# Pg02__AM335X_Section_1.net
KiCad netlist of a schematic drawn in Altium Designer
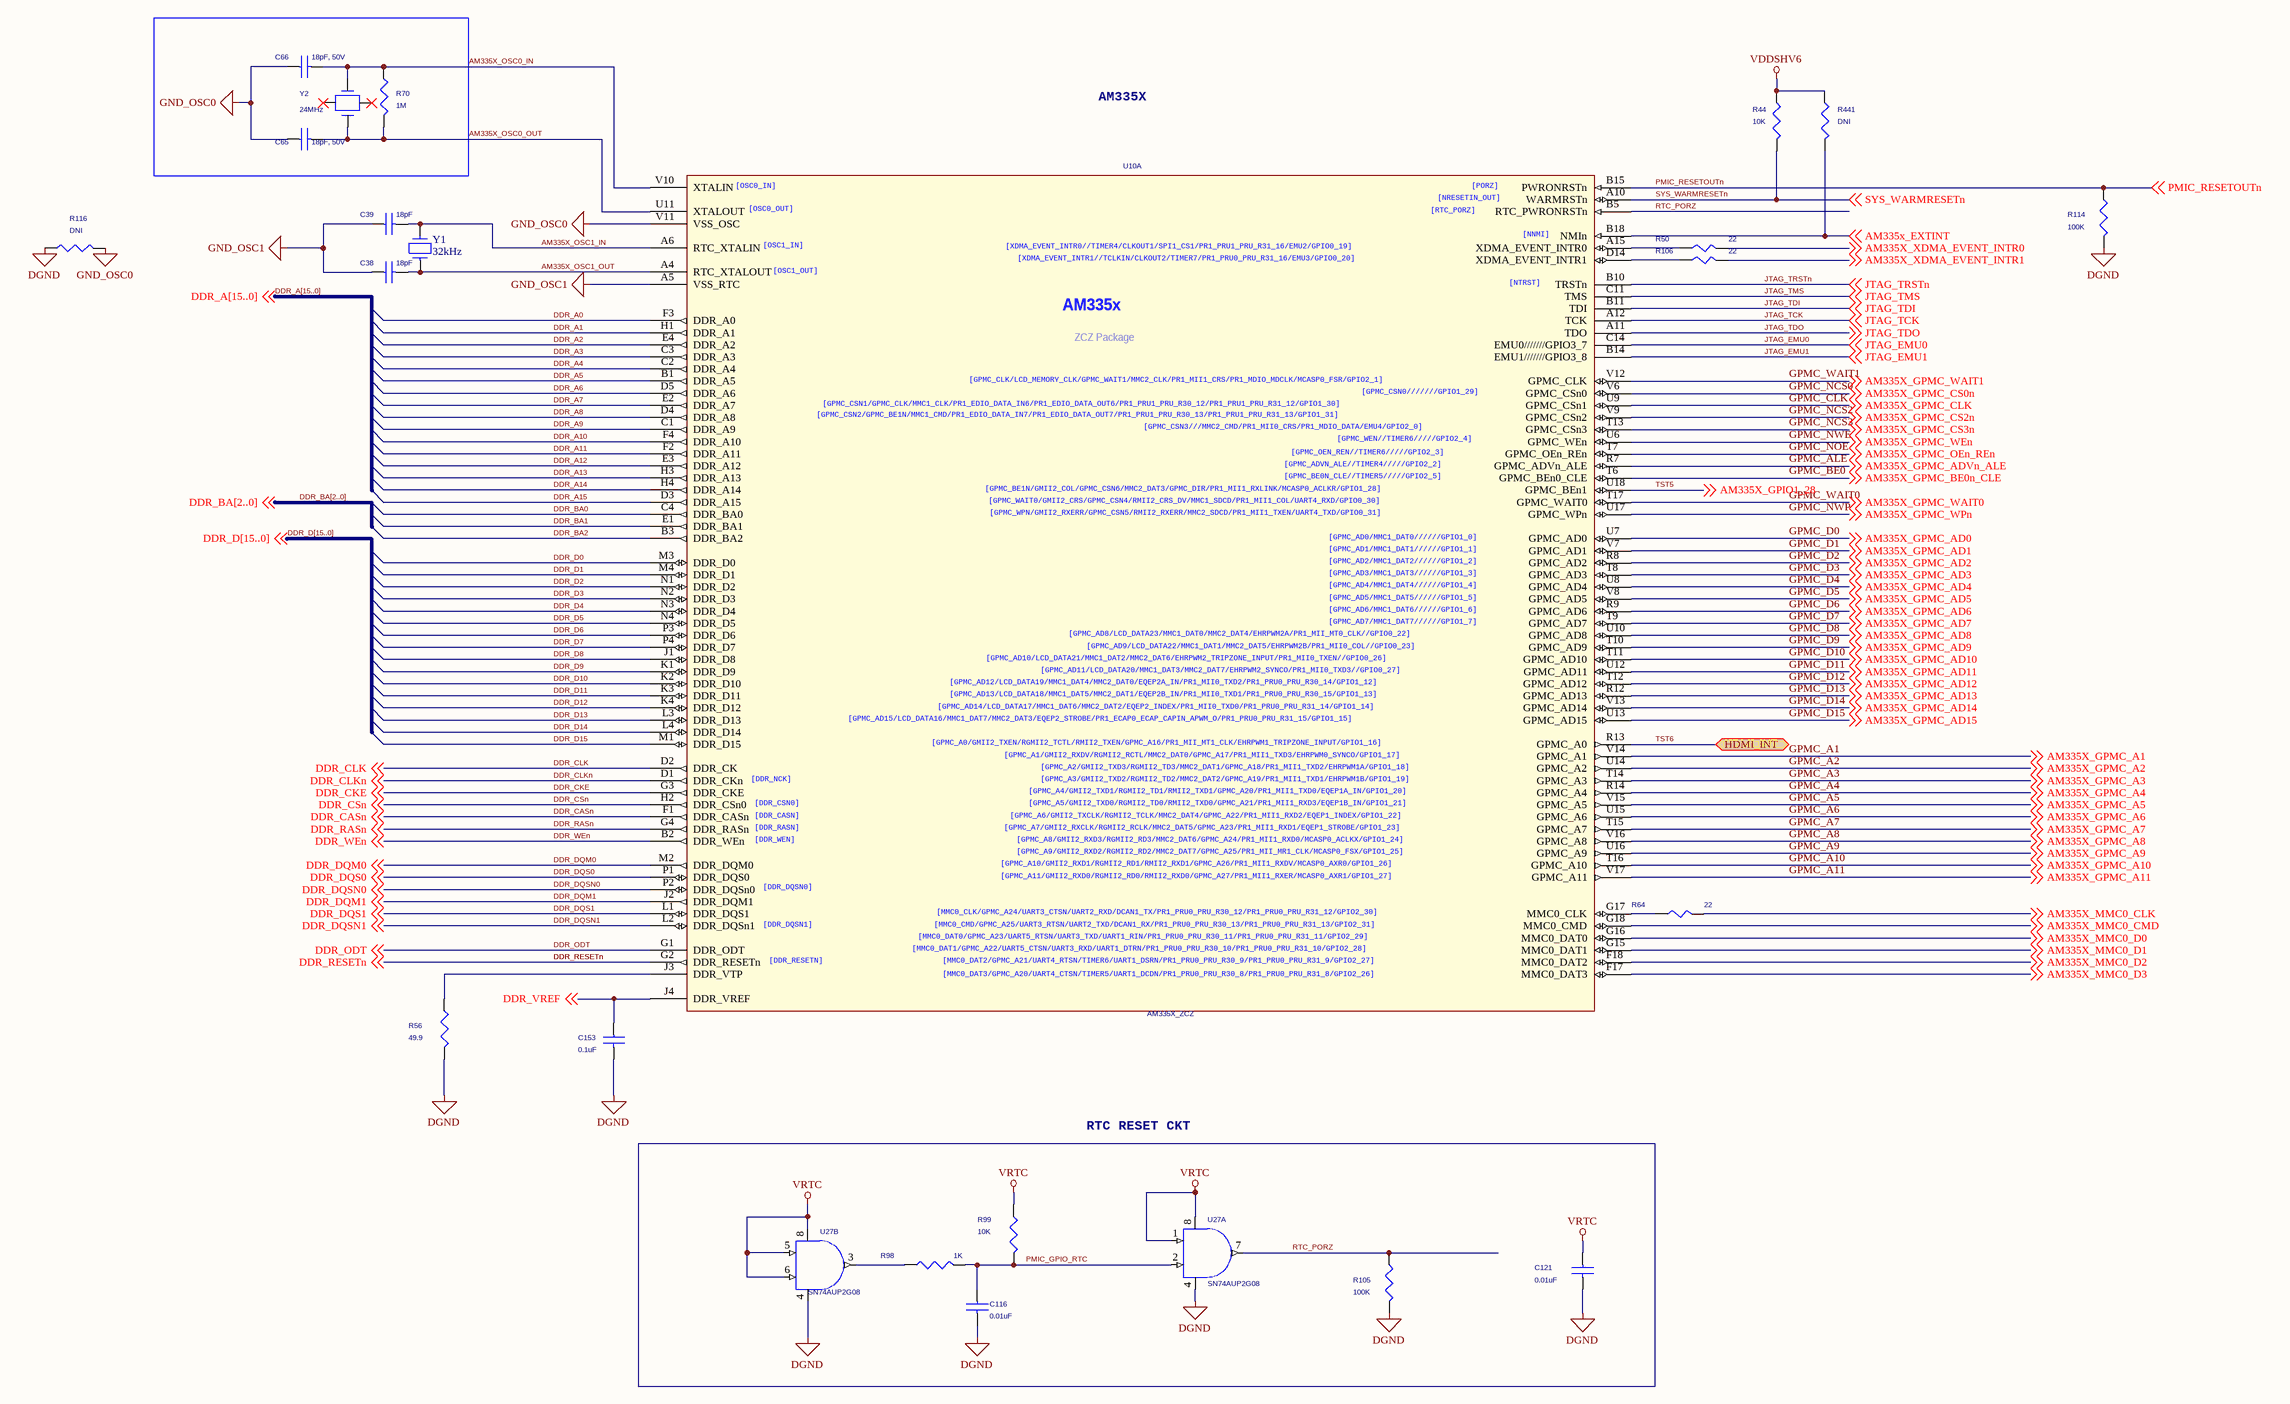
[diagram p0: Pg02_ AM335X Section 1 .SchDoc]

(export (version "E")
  (design (tool "Eeschema 10.0.6"))
  (components
    (comp (ref "C38")
      (value "18pF")
      (footprint "SM-7351-CAP-0402")
      (description "Capacitor 22pF 50V 10% 0402")
      (fields (field (name "MFR") "Panasonic") (field (name "TIINTPARTNUMBER") "1C0020"))
      (libsource (lib "*") (part "22pFCapacitor50V10%SMD0402"))
    )
    (comp (ref "C39")
      (value "18pF")
      (footprint "SM-7351-CAP-0402")
      (description "Capacitor 22pF 50V 10% 0402")
      (fields (field (name "MFR") "Panasonic") (field (name "TIINTPARTNUMBER") "1C0020"))
      (libsource (lib "*") (part "22pFCapacitor50V10%SMD0402"))
    )
    (comp (ref "C65")
      (value "18pF, 50V")
      (footprint "SM-7351-CAP-0402")
      (fields (field (name "MFR") "TDK") (field (name "TIINTPARTNUMBER") "1C0119"))
      (libsource (lib "*") (part "18pFCapacitor50V5%0402"))
    )
    (comp (ref "C66")
      (value "18pF, 50V")
      (footprint "SM-7351-CAP-0402")
      (fields (field (name "MFR") "TDK") (field (name "TIINTPARTNUMBER") "1C0119"))
      (libsource (lib "*") (part "18pFCapacitor50V5%0402"))
    )
    (comp (ref "C116")
      (value "0.01uF")
      (footprint "SM-7351-CAP-0402")
      (fields (field (name "MFR") "Panasonic") (field (name "TIINTPARTNUMBER") "1C0012"))
      (libsource (lib "*") (part "0.01uFCapacitor16V10%0402"))
    )
    (comp (ref "C121")
      (value "0.01uF")
      (footprint "SM-7351-CAP-0402")
      (fields (field (name "MFR") "Panasonic") (field (name "TIINTPARTNUMBER") "1C0012"))
      (libsource (lib "*") (part "0.01uFCapacitor16V10%0402"))
    )
    (comp (ref "C153")
      (value "0.1uF")
      (footprint "SM-7351-CAP-0402")
      (fields (field (name "TIINTPARTNUMBER") "1C0089") (field (name "MFR") "Kemet"))
      (libsource (lib "*") (part "0.1uFCapacitor16V10%0402_Dup1"))
    )
    (comp (ref "R44")
      (value "10K")
      (footprint "SM-7351-RES-0402")
      (description "Resistor 10Kohm 1/16W 5% 0402")
      (fields (field (name "TIINTPARTNUMBER") "1R0168") (field (name "MFR") "Rohm"))
      (libsource (lib "*") (part "10KOhmResistor1/16W0402_Dup1"))
    )
    (comp (ref "R50")
      (value "22")
      (footprint "SM-7351-RES-0402")
      (description "Resistor 22 ohm 1/16W 1% 0402")
      (fields (field (name "MFR") "ROHM") (field (name "TIINTPARTNUMBER") "1R0175"))
      (libsource (lib "*") (part "22OhmResistor1/16W1%0402"))
    )
    (comp (ref "R56")
      (value "49.9")
      (footprint "smd_melf0102")
      (fields (field (name "MFR") "Vishay") (field (name "TIINTPARTNUMBER") "1R0243"))
      (libsource (lib "*") (part "49.9ohm1/3W1%SMDMELF0102"))
    )
    (comp (ref "R64")
      (value "22")
      (footprint "SM-7351-RES-0402")
      (description "Resistor 22 ohm 1/16W 1% 0402")
      (fields (field (name "MFR") "ROHM") (field (name "TIINTPARTNUMBER") "1R0175"))
      (libsource (lib "*") (part "22OhmResistor1/16W1%0402"))
    )
    (comp (ref "R70")
      (value "1M")
      (footprint "SM-7351-RES-0402")
      (fields (field (name "MFR") "Stackpole Electronics") (field (name "TIINTPARTNUMBER") "1R0182"))
      (libsource (lib "*") (part "1MOhmResistor1/16W0402"))
    )
    (comp (ref "R98")
      (value "1K")
      (footprint "SM-7351-RES-0402")
      (description "Resistor 1Kohm 1/16W 5% 0402")
      (fields (field (name "MFR") "Panasonic") (field (name "TIINTPARTNUMBER") "1R0027"))
      (libsource (lib "*") (part "1KOhmResistor1/16W0402"))
    )
    (comp (ref "R99")
      (value "10K")
      (footprint "SM-7351-RES-0402")
      (description "Resistor 10Kohm 1/16W 5% 0402")
      (fields (field (name "MFR") "Rohm") (field (name "TIINTPARTNUMBER") "1R0168"))
      (libsource (lib "*") (part "10KOhmResistor1/16W0402"))
    )
    (comp (ref "R105")
      (value "100K")
      (footprint "SM-7351-RES-0402")
      (fields (field (name "TIINTPARTNUMBER") "1R0181") (field (name "MFR") "Stackpole Electronics"))
      (libsource (lib "*") (part "100KOhmResistor1/16W0402"))
    )
    (comp (ref "R106")
      (value "22")
      (footprint "SM-7351-RES-0402")
      (description "Resistor 22 ohm 1/16W 1% 0402")
      (fields (field (name "MFR") "ROHM") (field (name "TIINTPARTNUMBER") "1R0175"))
      (libsource (lib "*") (part "22OhmResistor1/16W1%0402"))
    )
    (comp (ref "R114")
      (value "100K")
      (footprint "SM-7351-RES-0402")
      (fields (field (name "TIINTPARTNUMBER") "1R0181") (field (name "MFR") "Stackpole Electronics"))
      (libsource (lib "*") (part "100KOhmResistor1/16W0402"))
    )
    (comp (ref "R116")
      (value "DNI")
      (footprint "SM-7351-RES-0402")
      (fields (field (name "MFR") "Stackpole Electronics") (field (name "TIINTPARTNUMBER") "1R0182"))
      (libsource (lib "*") (part "1MOhmResistor1/16W0402"))
    )
    (comp (ref "R441")
      (value "DNI")
      (footprint "SM-7351-RES-0402")
      (description "Resistor 10Kohm 1/16W 5% 0402")
      (fields (field (name "TIINTPARTNUMBER") "1R0168") (field (name "MFR") "Rohm"))
      (libsource (lib "*") (part "10KOhmResistor1/16W0402_Dup1"))
    )
    (comp (ref "U10")
      (value "AM335X_ZCZ")
      (footprint "BGA15X15-324-55M")
      (fields (field (name "TIINTPARTNUMBER") "1A0242") (field (name "MFR") "TI"))
      (libsource (lib "*") (part "AM335X_15mmx15mm"))
    )
    (comp (ref "U27")
      (value "SN74AUP2G08")
      (footprint "U_8_DCU")
      (description "Low Power Dual AND Gate")
      (fields (field (name "TIINTPARTNUMBER") "1A0249") (field (name "MFR") "TI"))
      (libsource (lib "*") (part "SN74AUP2G08"))
    )
    (comp (ref "Y1")
      (value "32kHz")
      (footprint "Xtal 3215")
      (description "CRYSTAL")
      (libsource (lib "Fireflash_B") (part "CRYSTAL"))
    )
    (comp (ref "Y2")
      (value "24MHz")
      (footprint "XTAL4_3P2X2P5_SMD")
      (fields (field (name "MFR") "Citizen") (field (name "TIINTPARTNUMBER") "1Y0039"))
      (libsource (lib "*") (part "Crystal24MHz18PFsmd_0"))
    )
  )
  (nets
    (net (code "1") (name "/AM335X_OSC0_IN") (class "Default")
      (node (ref "C66") (pin "2") (pinfunction "2_2") (pintype "passive"))
      (node (ref "R70") (pin "2") (pinfunction "P2_2") (pintype "passive"))
      (node (ref "U10") (pin "V10") (pinfunction "XTALIN_V10") (pintype "passive"))
      (node (ref "Y2") (pin "3") (pinfunction "3_3") (pintype "passive"))
    )
    (net (code "2") (name "/AM335X_OSC0_OUT") (class "Default")
      (node (ref "C65") (pin "2") (pinfunction "2_2") (pintype "passive"))
      (node (ref "R70") (pin "1") (pinfunction "P1_1") (pintype "passive"))
      (node (ref "U10") (pin "U11") (pinfunction "XTALOUT_U11") (pintype "passive"))
      (node (ref "Y2") (pin "1") (pinfunction "1_1") (pintype "passive"))
    )
    (net (code "3") (name "/AM335X_OSC1_IN") (class "Default")
      (node (ref "C39") (pin "2") (pinfunction "2_2") (pintype "passive"))
      (node (ref "U10") (pin "A6") (pinfunction "RTC_XTALIN_A6") (pintype "passive"))
      (node (ref "Y1") (pin "2") (pintype "passive"))
    )
    (net (code "4") (name "/AM335X_OSC1_OUT") (class "Default")
      (node (ref "C38") (pin "2") (pinfunction "2_2") (pintype "passive"))
      (node (ref "U10") (pin "A4") (pinfunction "RTC_XTALOUT_A4") (pintype "passive"))
      (node (ref "Y1") (pin "1") (pintype "passive"))
    )
    (net (code "5") (name "/PMIC_GPIO_RTC") (class "Default")
      (node (ref "C116") (pin "1") (pinfunction "1_1") (pintype "passive"))
      (node (ref "R98") (pin "1") (pinfunction "P1_1") (pintype "passive"))
      (node (ref "R99") (pin "1") (pinfunction "P1_1") (pintype "passive"))
      (node (ref "U27") (pin "2") (pinfunction "2B_2") (pintype "input"))
    )
    (net (code "6") (name "/RTC_PORZ") (class "Default")
      (node (ref "R105") (pin "2") (pinfunction "P2_2") (pintype "passive"))
      (node (ref "U10") (pin "B5") (pinfunction "RTC_PWRONRSTn_B5") (pintype "input"))
      (node (ref "U27") (pin "7") (pinfunction "2Y_7") (pintype "output"))
    )
    (net (code "7") (name "/TST6") (class "Default")
      (node (ref "U10") (pin "R13") (pinfunction "GPMC_A0_R13") (pintype "output"))
    )
    (net (code "8") (name "AM335X_GPIO1_28") (class "Default")
      (node (ref "U10") (pin "U18") (pinfunction "GPMC_BEn1_U18") (pintype "bidirectional"))
    )
    (net (code "9") (name "AM335X_GPMC_A1") (class "Default")
      (node (ref "U10") (pin "V14") (pinfunction "GPMC_A1_V14") (pintype "output"))
    )
    (net (code "10") (name "AM335X_GPMC_A2") (class "Default")
      (node (ref "U10") (pin "U14") (pinfunction "GPMC_A2_U14") (pintype "output"))
    )
    (net (code "11") (name "AM335X_GPMC_A3") (class "Default")
      (node (ref "U10") (pin "T14") (pinfunction "GPMC_A3_T14") (pintype "output"))
    )
    (net (code "12") (name "AM335X_GPMC_A4") (class "Default")
      (node (ref "U10") (pin "R14") (pinfunction "GPMC_A4_R14") (pintype "output"))
    )
    (net (code "13") (name "AM335X_GPMC_A5") (class "Default")
      (node (ref "U10") (pin "V15") (pinfunction "GPMC_A5_V15") (pintype "output"))
    )
    (net (code "14") (name "AM335X_GPMC_A6") (class "Default")
      (node (ref "U10") (pin "U15") (pinfunction "GPMC_A6_U15") (pintype "output"))
    )
    (net (code "15") (name "AM335X_GPMC_A7") (class "Default")
      (node (ref "U10") (pin "T15") (pinfunction "GPMC_A7_T15") (pintype "output"))
    )
    (net (code "16") (name "AM335X_GPMC_A8") (class "Default")
      (node (ref "U10") (pin "V16") (pinfunction "GPMC_A8_V16") (pintype "output"))
    )
    (net (code "17") (name "AM335X_GPMC_A9") (class "Default")
      (node (ref "U10") (pin "U16") (pinfunction "GPMC_A9_U16") (pintype "output"))
    )
    (net (code "18") (name "AM335X_GPMC_A10") (class "Default")
      (node (ref "U10") (pin "T16") (pinfunction "GPMC_A10_T16") (pintype "output"))
    )
    (net (code "19") (name "AM335X_GPMC_A11") (class "Default")
      (node (ref "U10") (pin "V17") (pinfunction "GPMC_A11_V17") (pintype "output"))
    )
    (net (code "20") (name "AM335X_GPMC_AD0") (class "Default")
      (node (ref "U10") (pin "U7") (pinfunction "GPMC_AD0_U7") (pintype "bidirectional"))
    )
    (net (code "21") (name "AM335X_GPMC_AD1") (class "Default")
      (node (ref "U10") (pin "V7") (pinfunction "GPMC_AD1_V7") (pintype "bidirectional"))
    )
    (net (code "22") (name "AM335X_GPMC_AD2") (class "Default")
      (node (ref "U10") (pin "R8") (pinfunction "GPMC_AD2_R8") (pintype "bidirectional"))
    )
    (net (code "23") (name "AM335X_GPMC_AD3") (class "Default")
      (node (ref "U10") (pin "T8") (pinfunction "GPMC_AD3_T8") (pintype "bidirectional"))
    )
    (net (code "24") (name "AM335X_GPMC_AD4") (class "Default")
      (node (ref "U10") (pin "U8") (pinfunction "GPMC_AD4_U8") (pintype "bidirectional"))
    )
    (net (code "25") (name "AM335X_GPMC_AD5") (class "Default")
      (node (ref "U10") (pin "V8") (pinfunction "GPMC_AD5_V8") (pintype "bidirectional"))
    )
    (net (code "26") (name "AM335X_GPMC_AD6") (class "Default")
      (node (ref "U10") (pin "R9") (pinfunction "GPMC_AD6_R9") (pintype "bidirectional"))
    )
    (net (code "27") (name "AM335X_GPMC_AD7") (class "Default")
      (node (ref "U10") (pin "T9") (pinfunction "GPMC_AD7_T9") (pintype "bidirectional"))
    )
    (net (code "28") (name "AM335X_GPMC_AD8") (class "Default")
      (node (ref "U10") (pin "U10") (pinfunction "GPMC_AD8_U10") (pintype "bidirectional"))
    )
    (net (code "29") (name "AM335X_GPMC_AD9") (class "Default")
      (node (ref "U10") (pin "T10") (pinfunction "GPMC_AD9_T10") (pintype "bidirectional"))
    )
    (net (code "30") (name "AM335X_GPMC_AD10") (class "Default")
      (node (ref "U10") (pin "T11") (pinfunction "GPMC_AD10_T11") (pintype "bidirectional"))
    )
    (net (code "31") (name "AM335X_GPMC_AD11") (class "Default")
      (node (ref "U10") (pin "U12") (pinfunction "GPMC_AD11_U12") (pintype "bidirectional"))
    )
    (net (code "32") (name "AM335X_GPMC_AD12") (class "Default")
      (node (ref "U10") (pin "T12") (pinfunction "GPMC_AD12_T12") (pintype "bidirectional"))
    )
    (net (code "33") (name "AM335X_GPMC_AD13") (class "Default")
      (node (ref "U10") (pin "R12") (pinfunction "GPMC_AD13_R12") (pintype "bidirectional"))
    )
    (net (code "34") (name "AM335X_GPMC_AD14") (class "Default")
      (node (ref "U10") (pin "V13") (pinfunction "GPMC_AD14_V13") (pintype "bidirectional"))
    )
    (net (code "35") (name "AM335X_GPMC_AD15") (class "Default")
      (node (ref "U10") (pin "U13") (pinfunction "GPMC_AD15_U13") (pintype "bidirectional"))
    )
    (net (code "36") (name "AM335X_GPMC_ADVn_ALE") (class "Default")
      (node (ref "U10") (pin "R7") (pinfunction "GPMC_ADVn_ALE_R7") (pintype "bidirectional"))
    )
    (net (code "37") (name "AM335X_GPMC_BE0n_CLE") (class "Default")
      (node (ref "U10") (pin "T6") (pinfunction "GPMC_BEn0_CLE_T6") (pintype "bidirectional"))
    )
    (net (code "38") (name "AM335X_GPMC_CLK") (class "Default")
      (node (ref "U10") (pin "U9") (pinfunction "GPMC_CSn1_U9") (pintype "bidirectional"))
    )
    (net (code "39") (name "AM335X_GPMC_CS0n") (class "Default")
      (node (ref "U10") (pin "V6") (pinfunction "GPMC_CSn0_V6") (pintype "bidirectional"))
    )
    (net (code "40") (name "AM335X_GPMC_CS2n") (class "Default")
      (node (ref "U10") (pin "V9") (pinfunction "GPMC_CSn2_V9") (pintype "bidirectional"))
    )
    (net (code "41") (name "AM335X_GPMC_CS3n") (class "Default")
      (node (ref "U10") (pin "T13") (pinfunction "GPMC_CSn3_T13") (pintype "bidirectional"))
    )
    (net (code "42") (name "AM335X_GPMC_OEn_REn") (class "Default")
      (node (ref "U10") (pin "T7") (pinfunction "GPMC_OEn_REn_T7") (pintype "bidirectional"))
    )
    (net (code "43") (name "AM335X_GPMC_WAIT0") (class "Default")
      (node (ref "U10") (pin "T17") (pinfunction "GPMC_WAIT0_T17") (pintype "bidirectional"))
    )
    (net (code "44") (name "AM335X_GPMC_WAIT1") (class "Default")
      (node (ref "U10") (pin "V12") (pinfunction "GPMC_CLK_V12") (pintype "bidirectional"))
    )
    (net (code "45") (name "AM335X_GPMC_WEn") (class "Default")
      (node (ref "U10") (pin "U6") (pinfunction "GPMC_WEn_U6") (pintype "bidirectional"))
    )
    (net (code "46") (name "AM335X_GPMC_WPn") (class "Default")
      (node (ref "U10") (pin "U17") (pinfunction "GPMC_WPn_U17") (pintype "bidirectional"))
    )
    (net (code "47") (name "AM335X_MMC0_CLK") (class "Default")
      (node (ref "R64") (pin "1") (pinfunction "P1_1") (pintype "passive"))
    )
    (net (code "48") (name "AM335X_MMC0_CMD") (class "Default")
      (node (ref "U10") (pin "G18") (pinfunction "MMC0_CMD_G18") (pintype "bidirectional"))
    )
    (net (code "49") (name "AM335X_MMC0_D0") (class "Default")
      (node (ref "U10") (pin "G16") (pinfunction "MMC0_DAT0_G16") (pintype "bidirectional"))
    )
    (net (code "50") (name "AM335X_MMC0_D1") (class "Default")
      (node (ref "U10") (pin "G15") (pinfunction "MMC0_DAT1_G15") (pintype "bidirectional"))
    )
    (net (code "51") (name "AM335X_MMC0_D2") (class "Default")
      (node (ref "U10") (pin "F18") (pinfunction "MMC0_DAT2_F18") (pintype "bidirectional"))
    )
    (net (code "52") (name "AM335X_MMC0_D3") (class "Default")
      (node (ref "U10") (pin "F17") (pinfunction "MMC0_DAT3_F17") (pintype "bidirectional"))
    )
    (net (code "53") (name "AM335X_XDMA_EVENT_INTR0") (class "Default")
      (node (ref "R50") (pin "1") (pinfunction "P1_1") (pintype "passive"))
    )
    (net (code "54") (name "AM335X_XDMA_EVENT_INTR1") (class "Default")
      (node (ref "R106") (pin "1") (pinfunction "P1_1") (pintype "passive"))
    )
    (net (code "55") (name "AM335x_EXTINT") (class "Default")
      (node (ref "R441") (pin "1") (pinfunction "P1_1") (pintype "passive"))
      (node (ref "U10") (pin "B18") (pinfunction "NMIn_B18") (pintype "input"))
    )
    (net (code "56") (name "DDR_A0") (class "Default")
      (node (ref "U10") (pin "F3") (pinfunction "DDR_A0_F3") (pintype "output"))
    )
    (net (code "57") (name "DDR_A1") (class "Default")
      (node (ref "U10") (pin "H1") (pinfunction "DDR_A1_H1") (pintype "output"))
    )
    (net (code "58") (name "DDR_A2") (class "Default")
      (node (ref "U10") (pin "E4") (pinfunction "DDR_A2_E4") (pintype "output"))
    )
    (net (code "59") (name "DDR_A3") (class "Default")
      (node (ref "U10") (pin "C3") (pinfunction "DDR_A3_C3") (pintype "output"))
    )
    (net (code "60") (name "DDR_A4") (class "Default")
      (node (ref "U10") (pin "C2") (pinfunction "DDR_A4_C2") (pintype "output"))
    )
    (net (code "61") (name "DDR_A5") (class "Default")
      (node (ref "U10") (pin "B1") (pinfunction "DDR_A5_B1") (pintype "output"))
    )
    (net (code "62") (name "DDR_A6") (class "Default")
      (node (ref "U10") (pin "D5") (pinfunction "DDR_A6_D5") (pintype "output"))
    )
    (net (code "63") (name "DDR_A7") (class "Default")
      (node (ref "U10") (pin "E2") (pinfunction "DDR_A7_E2") (pintype "output"))
    )
    (net (code "64") (name "DDR_A8") (class "Default")
      (node (ref "U10") (pin "D4") (pinfunction "DDR_A8_D4") (pintype "output"))
    )
    (net (code "65") (name "DDR_A9") (class "Default")
      (node (ref "U10") (pin "C1") (pinfunction "DDR_A9_C1") (pintype "output"))
    )
    (net (code "66") (name "DDR_A10") (class "Default")
      (node (ref "U10") (pin "F4") (pinfunction "DDR_A10_F4") (pintype "output"))
    )
    (net (code "67") (name "DDR_A11") (class "Default")
      (node (ref "U10") (pin "F2") (pinfunction "DDR_A11_F2") (pintype "output"))
    )
    (net (code "68") (name "DDR_A12") (class "Default")
      (node (ref "U10") (pin "E3") (pinfunction "DDR_A12_E3") (pintype "output"))
    )
    (net (code "69") (name "DDR_A13") (class "Default")
      (node (ref "U10") (pin "H3") (pinfunction "DDR_A13_H3") (pintype "output"))
    )
    (net (code "70") (name "DDR_A14") (class "Default")
      (node (ref "U10") (pin "H4") (pinfunction "DDR_A14_H4") (pintype "output"))
    )
    (net (code "71") (name "DDR_A15") (class "Default")
      (node (ref "U10") (pin "D3") (pinfunction "DDR_A15_D3") (pintype "output"))
    )
    (net (code "73") (name "DDR_BA0") (class "Default")
      (node (ref "U10") (pin "C4") (pinfunction "DDR_BA0_C4") (pintype "output"))
    )
    (net (code "74") (name "DDR_BA1") (class "Default")
      (node (ref "U10") (pin "E1") (pinfunction "DDR_BA1_E1") (pintype "output"))
    )
    (net (code "75") (name "DDR_BA2") (class "Default")
      (node (ref "U10") (pin "B3") (pinfunction "DDR_BA2_B3") (pintype "output"))
    )
    (net (code "77") (name "DDR_CASn") (class "Default")
      (node (ref "U10") (pin "F1") (pinfunction "DDR_CASn_F1") (pintype "output"))
    )
    (net (code "78") (name "DDR_CKE") (class "Default")
      (node (ref "U10") (pin "G3") (pinfunction "DDR_CKE_G3") (pintype "output"))
    )
    (net (code "79") (name "DDR_CLK") (class "Default")
      (node (ref "U10") (pin "D2") (pinfunction "DDR_CK_D2") (pintype "output"))
    )
    (net (code "80") (name "DDR_CLKn") (class "Default")
      (node (ref "U10") (pin "D1") (pinfunction "DDR_CKn_D1") (pintype "output"))
    )
    (net (code "81") (name "DDR_CSn") (class "Default")
      (node (ref "U10") (pin "H2") (pinfunction "DDR_CSn0_H2") (pintype "output"))
    )
    (net (code "82") (name "DDR_D0") (class "Default")
      (node (ref "U10") (pin "M3") (pinfunction "DDR_D0_M3") (pintype "bidirectional"))
    )
    (net (code "83") (name "DDR_D1") (class "Default")
      (node (ref "U10") (pin "M4") (pinfunction "DDR_D1_M4") (pintype "bidirectional"))
    )
    (net (code "84") (name "DDR_D2") (class "Default")
      (node (ref "U10") (pin "N1") (pinfunction "DDR_D2_N1") (pintype "bidirectional"))
    )
    (net (code "85") (name "DDR_D3") (class "Default")
      (node (ref "U10") (pin "N2") (pinfunction "DDR_D3_N2") (pintype "bidirectional"))
    )
    (net (code "86") (name "DDR_D4") (class "Default")
      (node (ref "U10") (pin "N3") (pinfunction "DDR_D4_N3") (pintype "bidirectional"))
    )
    (net (code "87") (name "DDR_D5") (class "Default")
      (node (ref "U10") (pin "N4") (pinfunction "DDR_D5_N4") (pintype "bidirectional"))
    )
    (net (code "88") (name "DDR_D6") (class "Default")
      (node (ref "U10") (pin "P3") (pinfunction "DDR_D6_P3") (pintype "bidirectional"))
    )
    (net (code "89") (name "DDR_D7") (class "Default")
      (node (ref "U10") (pin "P4") (pinfunction "DDR_D7_P4") (pintype "bidirectional"))
    )
    (net (code "90") (name "DDR_D8") (class "Default")
      (node (ref "U10") (pin "J1") (pinfunction "DDR_D8_J1") (pintype "bidirectional"))
    )
    (net (code "91") (name "DDR_D9") (class "Default")
      (node (ref "U10") (pin "K1") (pinfunction "DDR_D9_K1") (pintype "bidirectional"))
    )
    (net (code "92") (name "DDR_D10") (class "Default")
      (node (ref "U10") (pin "K2") (pinfunction "DDR_D10_K2") (pintype "bidirectional"))
    )
    (net (code "93") (name "DDR_D11") (class "Default")
      (node (ref "U10") (pin "K3") (pinfunction "DDR_D11_K3") (pintype "bidirectional"))
    )
    (net (code "94") (name "DDR_D12") (class "Default")
      (node (ref "U10") (pin "K4") (pinfunction "DDR_D12_K4") (pintype "bidirectional"))
    )
    (net (code "95") (name "DDR_D13") (class "Default")
      (node (ref "U10") (pin "L3") (pinfunction "DDR_D13_L3") (pintype "bidirectional"))
    )
    (net (code "96") (name "DDR_D14") (class "Default")
      (node (ref "U10") (pin "L4") (pinfunction "DDR_D14_L4") (pintype "bidirectional"))
    )
    (net (code "97") (name "DDR_D15") (class "Default")
      (node (ref "U10") (pin "M1") (pinfunction "DDR_D15_M1") (pintype "bidirectional"))
    )
    (net (code "98") (name "DDR_DQM0") (class "Default")
      (node (ref "U10") (pin "M2") (pinfunction "DDR_DQM0_M2") (pintype "output"))
    )
    (net (code "99") (name "DDR_DQM1") (class "Default")
      (node (ref "U10") (pin "J2") (pinfunction "DDR_DQM1_J2") (pintype "output"))
    )
    (net (code "100") (name "DDR_DQS0") (class "Default")
      (node (ref "U10") (pin "P1") (pinfunction "DDR_DQS0_P1") (pintype "bidirectional"))
    )
    (net (code "101") (name "DDR_DQS1") (class "Default")
      (node (ref "U10") (pin "L1") (pinfunction "DDR_DQS1_L1") (pintype "bidirectional"))
    )
    (net (code "102") (name "DDR_DQSN0") (class "Default")
      (node (ref "U10") (pin "P2") (pinfunction "DDR_DQSn0_P2") (pintype "bidirectional"))
    )
    (net (code "103") (name "DDR_DQSN1") (class "Default")
      (node (ref "U10") (pin "L2") (pinfunction "DDR_DQSn1_L2") (pintype "bidirectional"))
    )
    (net (code "105") (name "DDR_ODT") (class "Default")
      (node (ref "U10") (pin "G1") (pinfunction "DDR_ODT_G1") (pintype "passive"))
    )
    (net (code "106") (name "DDR_RASn") (class "Default")
      (node (ref "U10") (pin "G4") (pinfunction "DDR_RASn_G4") (pintype "output"))
    )
    (net (code "107") (name "DDR_RESETn") (class "Default")
      (node (ref "U10") (pin "G2") (pinfunction "DDR_RESETn_G2") (pintype "output"))
    )
    (net (code "108") (name "DDR_VREF") (class "Default")
      (node (ref "C153") (pin "1") (pinfunction "1_1") (pintype "passive"))
      (node (ref "U10") (pin "J4") (pinfunction "DDR_VREF_J4") (pintype "passive"))
    )
    (net (code "109") (name "DDR_WEn") (class "Default")
      (node (ref "U10") (pin "B2") (pinfunction "DDR_WEn_B2") (pintype "output"))
    )
    (net (code "110") (name "DGND") (class "Default")
      (node (ref "C116") (pin "2") (pinfunction "2_2") (pintype "passive"))
      (node (ref "C121") (pin "2") (pinfunction "2_2") (pintype "passive"))
      (node (ref "C153") (pin "2") (pinfunction "2_2") (pintype "passive"))
      (node (ref "R105") (pin "1") (pinfunction "P1_1") (pintype "passive"))
      (node (ref "R114") (pin "1") (pinfunction "P1_1") (pintype "passive"))
      (node (ref "R116") (pin "2") (pinfunction "P2_2") (pintype "passive"))
      (node (ref "R56") (pin "1") (pinfunction "P1_1") (pintype "passive"))
      (node (ref "U27") (pin "4") (pinfunction "GND_4") (pintype "power_in"))
    )
    (net (code "111") (name "GND_OSC0") (class "Default")
      (node (ref "C65") (pin "1") (pinfunction "1_1") (pintype "passive"))
      (node (ref "C66") (pin "1") (pinfunction "1_1") (pintype "passive"))
      (node (ref "R116") (pin "1") (pinfunction "P1_1") (pintype "passive"))
      (node (ref "U10") (pin "V11") (pinfunction "VSS_OSC_V11") (pintype "power_in"))
    )
    (net (code "112") (name "GND_OSC1") (class "Default")
      (node (ref "C38") (pin "1") (pinfunction "1_1") (pintype "passive"))
      (node (ref "C39") (pin "1") (pinfunction "1_1") (pintype "passive"))
      (node (ref "U10") (pin "A5") (pinfunction "VSS_RTC_A5") (pintype "power_in"))
    )
    (net (code "113") (name "JTAG_EMU0") (class "Default")
      (node (ref "U10") (pin "C14") (pinfunction "EMU0///////GPIO3_7_C14") (pintype "passive"))
    )
    (net (code "114") (name "JTAG_EMU1") (class "Default")
      (node (ref "U10") (pin "B14") (pinfunction "EMU1///////GPIO3_8_B14") (pintype "passive"))
    )
    (net (code "115") (name "JTAG_TCK") (class "Default")
      (node (ref "U10") (pin "A12") (pinfunction "TCK_A12") (pintype "passive"))
    )
    (net (code "116") (name "JTAG_TDI") (class "Default")
      (node (ref "U10") (pin "B11") (pinfunction "TDI_B11") (pintype "passive"))
    )
    (net (code "117") (name "JTAG_TDO") (class "Default")
      (node (ref "U10") (pin "A11") (pinfunction "TDO_A11") (pintype "passive"))
    )
    (net (code "118") (name "JTAG_TMS") (class "Default")
      (node (ref "U10") (pin "C11") (pinfunction "TMS_C11") (pintype "passive"))
    )
    (net (code "119") (name "JTAG_TRSTn") (class "Default")
      (node (ref "U10") (pin "B10") (pinfunction "TRSTn_B10") (pintype "passive"))
    )
    (net (code "120") (name "Net-(R50-P2)") (class "Default")
      (node (ref "R50") (pin "2") (pinfunction "P2_2") (pintype "passive"))
      (node (ref "U10") (pin "A15") (pinfunction "XDMA_EVENT_INTR0_A15") (pintype "bidirectional"))
    )
    (net (code "121") (name "Net-(R56-P2)") (class "Default")
      (node (ref "R56") (pin "2") (pinfunction "P2_2") (pintype "passive"))
      (node (ref "U10") (pin "J3") (pinfunction "DDR_VTP_J3") (pintype "passive"))
    )
    (net (code "122") (name "Net-(R64-P2)") (class "Default")
      (node (ref "R64") (pin "2") (pinfunction "P2_2") (pintype "passive"))
      (node (ref "U10") (pin "G17") (pinfunction "MMC0_CLK_G17") (pintype "bidirectional"))
    )
    (net (code "123") (name "Net-(R98-P2)") (class "Default")
      (node (ref "R98") (pin "2") (pinfunction "P2_2") (pintype "passive"))
      (node (ref "U27") (pin "3") (pinfunction "2Y_3") (pintype "output"))
    )
    (net (code "124") (name "Net-(R106-P2)") (class "Default")
      (node (ref "R106") (pin "2") (pinfunction "P2_2") (pintype "passive"))
      (node (ref "U10") (pin "D14") (pinfunction "XDMA_EVENT_INTR1_D14") (pintype "bidirectional"))
    )
    (net (code "125") (name "PMIC_RESETOUTn") (class "Default")
      (node (ref "R114") (pin "2") (pinfunction "P2_2") (pintype "passive"))
      (node (ref "U10") (pin "B15") (pinfunction "PWRONRSTn_B15") (pintype "input"))
    )
    (net (code "126") (name "SYS_WARMRESETn") (class "Default")
      (node (ref "R44") (pin "1") (pinfunction "P1_1") (pintype "passive"))
      (node (ref "U10") (pin "A10") (pinfunction "WARMRSTn_A10") (pintype "bidirectional"))
    )
    (net (code "127") (name "VDDSHV6") (class "Default")
      (node (ref "R44") (pin "2") (pinfunction "P2_2") (pintype "passive"))
      (node (ref "R441") (pin "2") (pinfunction "P2_2") (pintype "passive"))
    )
    (net (code "128") (name "VRTC") (class "Default")
      (node (ref "C121") (pin "1") (pinfunction "1_1") (pintype "passive"))
      (node (ref "R99") (pin "2") (pinfunction "P2_2") (pintype "passive"))
      (node (ref "U27") (pin "1") (pinfunction "2A_1") (pintype "input"))
      (node (ref "U27") (pin "5") (pinfunction "2A_5") (pintype "input"))
      (node (ref "U27") (pin "6") (pinfunction "2B_6") (pintype "input"))
      (node (ref "U27") (pin "8") (pinfunction "VCC_8") (pintype "power_in"))
    )
    (net (code "129") (name "unconnected-(Y2-NC0-Pad2)") (class "Default")
      (node (ref "Y2") (pin "2") (pinfunction "NC0_2") (pintype "passive+no_connect"))
    )
    (net (code "130") (name "unconnected-(Y2-NC1-Pad4)") (class "Default")
      (node (ref "Y2") (pin "4") (pinfunction "NC1_4") (pintype "passive+no_connect"))
    )
  )
)
